# DACV5.net
KiCad netlist of a schematic drawn in EAGLE
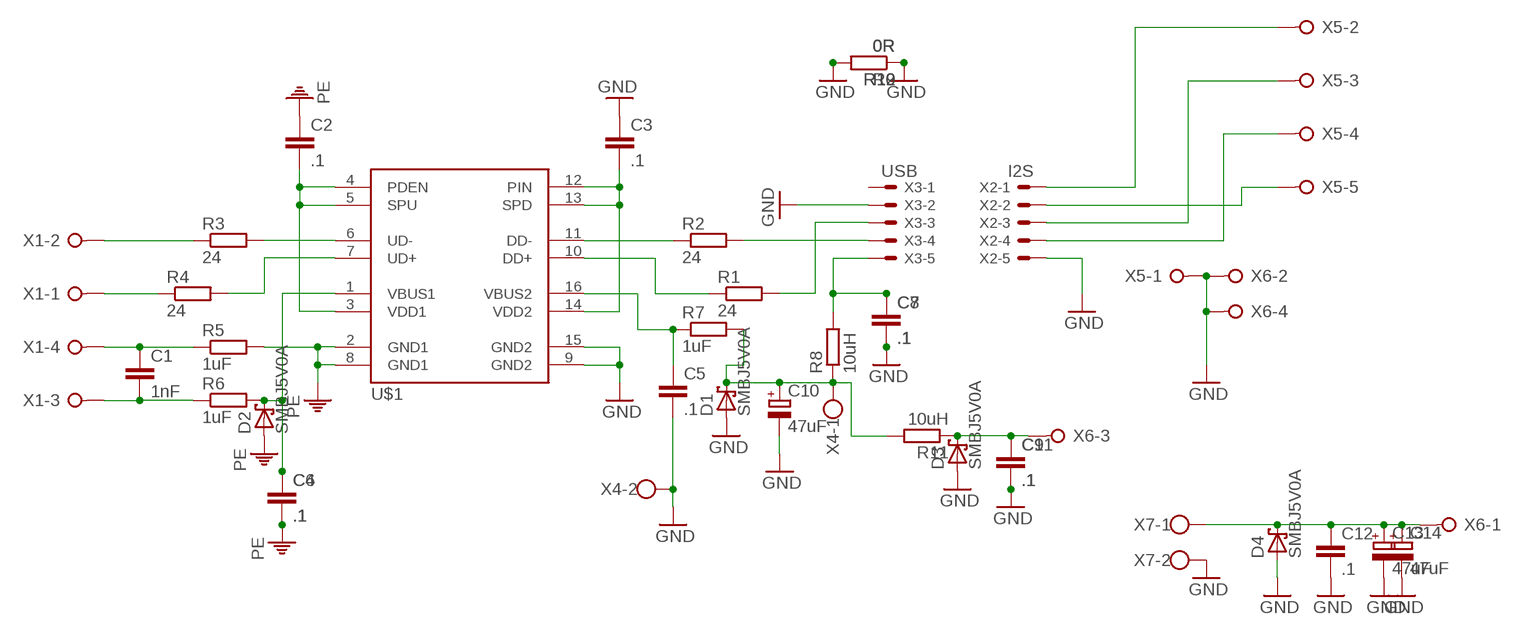
[diagram p0: schematic, sheet 1]

(export (version "E")
  (design (tool "Eeschema 10.0.6"))
  (components
    (comp (ref "C1")
      (value "1nF")
      (footprint "eagle-import:C1210")
      (libsource (lib "eagle-import") (part "C-EUC1210"))
    )
    (comp (ref "C2")
      (value ".1")
      (footprint "eagle-import:C1210")
      (libsource (lib "eagle-import") (part "C-EUC1210"))
    )
    (comp (ref "C3")
      (value ".1")
      (footprint "eagle-import:C1210")
      (libsource (lib "eagle-import") (part "C-EUC1210"))
    )
    (comp (ref "C4")
      (value ".1")
      (footprint "eagle-import:C1210")
      (libsource (lib "eagle-import") (part "C-EUC1210"))
    )
    (comp (ref "C5")
      (value ".1")
      (footprint "eagle-import:C1210")
      (libsource (lib "eagle-import") (part "C-EUC1210"))
    )
    (comp (ref "C6")
      (value ".1")
      (footprint "eagle-import:C1210")
      (libsource (lib "eagle-import") (part "C-EUC1210"))
    )
    (comp (ref "C7")
      (value ".1")
      (footprint "eagle-import:C1210")
      (libsource (lib "eagle-import") (part "C-EUC1210"))
    )
    (comp (ref "C8")
      (value ".1")
      (footprint "eagle-import:C1210")
      (libsource (lib "eagle-import") (part "C-EUC1210"))
    )
    (comp (ref "C9")
      (value ".1")
      (footprint "eagle-import:C1210")
      (libsource (lib "eagle-import") (part "C-EUC1210"))
    )
    (comp (ref "C10")
      (value "47uF")
      (footprint "eagle-import:E5-13")
      (libsource (lib "eagle-import") (part "CPOL-EUE5-13"))
    )
    (comp (ref "C11")
      (value ".1")
      (footprint "eagle-import:C1210")
      (libsource (lib "eagle-import") (part "C-EUC1210"))
    )
    (comp (ref "C12")
      (value ".1")
      (footprint "eagle-import:C1210")
      (libsource (lib "eagle-import") (part "C-EUC1210"))
    )
    (comp (ref "C13")
      (value "47uF")
      (footprint "eagle-import:E5-13")
      (libsource (lib "eagle-import") (part "CPOL-EUE5-13"))
    )
    (comp (ref "C14")
      (value "47uF")
      (footprint "eagle-import:E5-13")
      (libsource (lib "eagle-import") (part "CPOL-EUE5-13"))
    )
    (comp (ref "D1")
      (value "SMBJ5V0A")
      (footprint "eagle-import:SMB")
      (libsource (lib "eagle-import") (part "MBRS130LT3"))
    )
    (comp (ref "D2")
      (value "SMBJ5V0A")
      (footprint "eagle-import:SMB")
      (libsource (lib "eagle-import") (part "MBRS130LT3"))
    )
    (comp (ref "D3")
      (value "SMBJ5V0A")
      (footprint "eagle-import:SMB")
      (libsource (lib "eagle-import") (part "MBRS130LT3"))
    )
    (comp (ref "D4")
      (value "SMBJ5V0A")
      (footprint "eagle-import:SMB")
      (libsource (lib "eagle-import") (part "MBRS130LT3"))
    )
    (comp (ref "R1")
      (value "24")
      (footprint "eagle-import:R1210")
      (libsource (lib "eagle-import") (part "R-EU_R1210"))
    )
    (comp (ref "R2")
      (value "24")
      (footprint "eagle-import:R1210")
      (libsource (lib "eagle-import") (part "R-EU_R1210"))
    )
    (comp (ref "R3")
      (value "24")
      (footprint "eagle-import:R1210")
      (libsource (lib "eagle-import") (part "R-EU_R1210"))
    )
    (comp (ref "R4")
      (value "24")
      (footprint "eagle-import:R1210")
      (libsource (lib "eagle-import") (part "R-EU_R1210"))
    )
    (comp (ref "R5")
      (value "1uF")
      (footprint "eagle-import:R1210")
      (libsource (lib "eagle-import") (part "R-EU_R1210"))
    )
    (comp (ref "R6")
      (value "1uF")
      (footprint "eagle-import:R1210")
      (libsource (lib "eagle-import") (part "R-EU_R1210"))
    )
    (comp (ref "R7")
      (value "1uF")
      (footprint "eagle-import:R1210")
      (libsource (lib "eagle-import") (part "R-EU_R1210"))
    )
    (comp (ref "R8")
      (value "10uH")
      (footprint "eagle-import:0309_12")
      (libsource (lib "eagle-import") (part "R-EU_0309/12"))
    )
    (comp (ref "R9")
      (value "0R")
      (footprint "eagle-import:0309_12")
      (libsource (lib "eagle-import") (part "R-EU_0309/12"))
    )
    (comp (ref "R10")
      (value "0R")
      (footprint "eagle-import:0309_12")
      (libsource (lib "eagle-import") (part "R-EU_0309/12"))
    )
    (comp (ref "R11")
      (value "10uH")
      (footprint "eagle-import:0309_12")
      (libsource (lib "eagle-import") (part "R-EU_0309/12"))
    )
    (comp (ref "R12")
      (value "0R")
      (footprint "eagle-import:0309_12")
      (libsource (lib "eagle-import") (part "R-EU_0309/12"))
    )
    (comp (ref "U$1")
      (value "ADUM4160")
      (footprint "eagle-import:SO16W")
      (libsource (lib "eagle-import") (part "ADUM4160"))
    )
    (comp (ref "X1")
      (value "W237-04P")
      (footprint "eagle-import:W237-4P")
      (libsource (lib "eagle-import") (part "W237-04P"))
    )
    (comp (ref "X2")
      (value "I2S")
      (footprint "eagle-import:22-23-2051")
      (fields (field (name "MF") "MOLEX") (field (name "MPN") "22-23-2051"))
      (libsource (lib "eagle-import") (part "22-23-2051"))
    )
    (comp (ref "X3")
      (value "USB")
      (footprint "eagle-import:22-23-2051")
      (fields (field (name "MF") "MOLEX") (field (name "MPN") "22-23-2051"))
      (libsource (lib "eagle-import") (part "22-23-2051"))
    )
    (comp (ref "X4")
      (value "W237-102")
      (footprint "eagle-import:W237-102")
      (fields (field (name "MPN") "237-102"))
      (libsource (lib "eagle-import") (part "W237-102"))
    )
    (comp (ref "X5")
      (value "W237-05P")
      (footprint "eagle-import:W237-5P")
      (libsource (lib "eagle-import") (part "W237-05P"))
    )
    (comp (ref "X6")
      (value "W237-04P")
      (footprint "eagle-import:W237-4P")
      (libsource (lib "eagle-import") (part "W237-04P"))
    )
    (comp (ref "X7")
      (value "W237-102")
      (footprint "eagle-import:W237-102")
      (fields
        (field (name "MPN") "237-102")
        (field (name "MPN_1") "237-102")
        (field (name "OC_FARNELL") "unknown")
        (field (name "OC_NEWARK") "70K9898")
      )
      (libsource (lib "eagle-import") (part "W237-102"))
    )
  )
  (nets
    (net (code "1") (name "GND") (class "Default")
      (node (ref "C10") (pin "-") (pinfunction "-_-") (pintype "passive"))
      (node (ref "C11") (pin "2") (pinfunction "2_2") (pintype "passive"))
      (node (ref "C12") (pin "2") (pinfunction "2_2") (pintype "passive"))
      (node (ref "C13") (pin "-") (pinfunction "-_-") (pintype "passive"))
      (node (ref "C14") (pin "-") (pinfunction "-_-") (pintype "passive"))
      (node (ref "C3") (pin "1") (pinfunction "1_1") (pintype "passive"))
      (node (ref "C5") (pin "2") (pinfunction "2_2") (pintype "passive"))
      (node (ref "C7") (pin "2") (pinfunction "2_2") (pintype "passive"))
      (node (ref "C8") (pin "2") (pinfunction "2_2") (pintype "passive"))
      (node (ref "C9") (pin "2") (pinfunction "2_2") (pintype "passive"))
      (node (ref "D1") (pin "A") (pinfunction "A_A") (pintype "passive"))
      (node (ref "D3") (pin "A") (pinfunction "A_A") (pintype "passive"))
      (node (ref "D4") (pin "A") (pinfunction "A_A") (pintype "passive"))
      (node (ref "R10") (pin "1") (pinfunction "1_1") (pintype "passive"))
      (node (ref "R10") (pin "2") (pinfunction "2_2") (pintype "passive"))
      (node (ref "R12") (pin "1") (pinfunction "1_1") (pintype "passive"))
      (node (ref "R12") (pin "2") (pinfunction "2_2") (pintype "passive"))
      (node (ref "R9") (pin "1") (pinfunction "1_1") (pintype "passive"))
      (node (ref "R9") (pin "2") (pinfunction "2_2") (pintype "passive"))
      (node (ref "U$1") (pin "15") (pinfunction "GND2_15") (pintype "passive"))
      (node (ref "U$1") (pin "9") (pinfunction "GND2_9") (pintype "passive"))
      (node (ref "X2") (pin "5") (pinfunction "S_5") (pintype "passive"))
      (node (ref "X3") (pin "2") (pinfunction "S_2") (pintype "passive"))
      (node (ref "X4") (pin "2") (pinfunction "KL_2") (pintype "passive"))
      (node (ref "X5") (pin "1") (pinfunction "KL_1") (pintype "passive"))
      (node (ref "X6") (pin "2") (pinfunction "KL_2") (pintype "passive"))
      (node (ref "X6") (pin "4") (pinfunction "KL_4") (pintype "passive"))
      (node (ref "X7") (pin "2") (pinfunction "KL_2") (pintype "passive"))
    )
    (net (code "2") (name "Net-(U$1-DD+)") (class "Default")
      (node (ref "R1") (pin "1") (pinfunction "1_1") (pintype "passive"))
      (node (ref "U$1") (pin "10") (pinfunction "DD+_10") (pintype "bidirectional"))
    )
    (net (code "3") (name "Net-(U$1-DD-)") (class "Default")
      (node (ref "R2") (pin "1") (pinfunction "1_1") (pintype "passive"))
      (node (ref "U$1") (pin "11") (pinfunction "DD-_11") (pintype "bidirectional"))
    )
    (net (code "4") (name "Net-(U$1-PDEN)") (class "Default")
      (node (ref "C2") (pin "2") (pinfunction "2_2") (pintype "passive"))
      (node (ref "U$1") (pin "3") (pinfunction "VDD1_3") (pintype "power_in"))
      (node (ref "U$1") (pin "4") (pinfunction "PDEN_4") (pintype "input"))
      (node (ref "U$1") (pin "5") (pinfunction "SPU_5") (pintype "input"))
    )
    (net (code "5") (name "Net-(U$1-PIN)") (class "Default")
      (node (ref "C3") (pin "2") (pinfunction "2_2") (pintype "passive"))
      (node (ref "U$1") (pin "12") (pinfunction "PIN_12") (pintype "input"))
      (node (ref "U$1") (pin "13") (pinfunction "SPD_13") (pintype "input"))
      (node (ref "U$1") (pin "14") (pinfunction "VDD2_14") (pintype "power_in"))
    )
    (net (code "6") (name "Net-(U$1-UD+)") (class "Default")
      (node (ref "R4") (pin "2") (pinfunction "2_2") (pintype "passive"))
      (node (ref "U$1") (pin "7") (pinfunction "UD+_7") (pintype "bidirectional"))
    )
    (net (code "7") (name "Net-(U$1-UD-)") (class "Default")
      (node (ref "R3") (pin "2") (pinfunction "2_2") (pintype "passive"))
      (node (ref "U$1") (pin "6") (pinfunction "UD-_6") (pintype "bidirectional"))
    )
    (net (code "8") (name "Net-(U$1-VBUS1)") (class "Default")
      (node (ref "C4") (pin "1") (pinfunction "1_1") (pintype "passive"))
      (node (ref "C6") (pin "1") (pinfunction "1_1") (pintype "passive"))
      (node (ref "D2") (pin "C") (pinfunction "C_C") (pintype "passive"))
      (node (ref "R6") (pin "2") (pinfunction "2_2") (pintype "passive"))
      (node (ref "U$1") (pin "1") (pinfunction "VBUS1_1") (pintype "power_in"))
    )
    (net (code "9") (name "Net-(U$1-VBUS2)") (class "Default")
      (node (ref "C5") (pin "1") (pinfunction "1_1") (pintype "passive"))
      (node (ref "R7") (pin "1") (pinfunction "1_1") (pintype "passive"))
      (node (ref "U$1") (pin "16") (pinfunction "VBUS2_16") (pintype "power_in"))
    )
    (net (code "10") (name "Net-(X1A-KL)") (class "Default")
      (node (ref "R4") (pin "1") (pinfunction "1_1") (pintype "passive"))
      (node (ref "X1") (pin "1") (pinfunction "KL_1") (pintype "passive"))
    )
    (net (code "11") (name "Net-(X1B-KL)") (class "Default")
      (node (ref "R3") (pin "1") (pinfunction "1_1") (pintype "passive"))
      (node (ref "X1") (pin "2") (pinfunction "KL_2") (pintype "passive"))
    )
    (net (code "12") (name "Net-(X1C-KL)") (class "Default")
      (node (ref "C1") (pin "2") (pinfunction "2_2") (pintype "passive"))
      (node (ref "R6") (pin "1") (pinfunction "1_1") (pintype "passive"))
      (node (ref "X1") (pin "3") (pinfunction "KL_3") (pintype "passive"))
    )
    (net (code "13") (name "Net-(X1D-KL)") (class "Default")
      (node (ref "C1") (pin "1") (pinfunction "1_1") (pintype "passive"))
      (node (ref "R5") (pin "1") (pinfunction "1_1") (pintype "passive"))
      (node (ref "X1") (pin "4") (pinfunction "KL_4") (pintype "passive"))
    )
    (net (code "14") (name "Net-(X2A-S)") (class "Default")
      (node (ref "X2") (pin "1") (pinfunction "S_1") (pintype "passive"))
      (node (ref "X5") (pin "2") (pinfunction "KL_2") (pintype "passive"))
    )
    (net (code "15") (name "Net-(X2B-S)") (class "Default")
      (node (ref "X2") (pin "2") (pinfunction "S_2") (pintype "passive"))
      (node (ref "X5") (pin "5") (pinfunction "KL_5") (pintype "passive"))
    )
    (net (code "16") (name "Net-(X2C-S)") (class "Default")
      (node (ref "X2") (pin "3") (pinfunction "S_3") (pintype "passive"))
      (node (ref "X5") (pin "3") (pinfunction "KL_3") (pintype "passive"))
    )
    (net (code "17") (name "Net-(X2D-S)") (class "Default")
      (node (ref "X2") (pin "4") (pinfunction "S_4") (pintype "passive"))
      (node (ref "X5") (pin "4") (pinfunction "KL_4") (pintype "passive"))
    )
    (net (code "18") (name "Net-(X3C-S)") (class "Default")
      (node (ref "R1") (pin "2") (pinfunction "2_2") (pintype "passive"))
      (node (ref "X3") (pin "3") (pinfunction "S_3") (pintype "passive"))
    )
    (net (code "19") (name "Net-(X3D-S)") (class "Default")
      (node (ref "R2") (pin "2") (pinfunction "2_2") (pintype "passive"))
      (node (ref "X3") (pin "4") (pinfunction "S_4") (pintype "passive"))
    )
    (net (code "20") (name "Net-(X3E-S)") (class "Default")
      (node (ref "C7") (pin "1") (pinfunction "1_1") (pintype "passive"))
      (node (ref "C8") (pin "1") (pinfunction "1_1") (pintype "passive"))
      (node (ref "R8") (pin "2") (pinfunction "2_2") (pintype "passive"))
      (node (ref "X3") (pin "5") (pinfunction "S_5") (pintype "passive"))
    )
    (net (code "21") (name "Net-(X4A-KL)") (class "Default")
      (node (ref "C10") (pin "+") (pinfunction "+_+") (pintype "passive"))
      (node (ref "D1") (pin "C") (pinfunction "C_C") (pintype "passive"))
      (node (ref "R11") (pin "2") (pinfunction "2_2") (pintype "passive"))
      (node (ref "R7") (pin "2") (pinfunction "2_2") (pintype "passive"))
      (node (ref "R8") (pin "1") (pinfunction "1_1") (pintype "passive"))
      (node (ref "X4") (pin "1") (pinfunction "KL_1") (pintype "passive"))
    )
    (net (code "22") (name "Net-(X6A-KL)") (class "Default")
      (node (ref "C12") (pin "1") (pinfunction "1_1") (pintype "passive"))
      (node (ref "C13") (pin "+") (pinfunction "+_+") (pintype "passive"))
      (node (ref "C14") (pin "+") (pinfunction "+_+") (pintype "passive"))
      (node (ref "D4") (pin "C") (pinfunction "C_C") (pintype "passive"))
      (node (ref "X6") (pin "1") (pinfunction "KL_1") (pintype "passive"))
      (node (ref "X7") (pin "1") (pinfunction "KL_1") (pintype "passive"))
    )
    (net (code "23") (name "Net-(X6C-KL)") (class "Default")
      (node (ref "C11") (pin "1") (pinfunction "1_1") (pintype "passive"))
      (node (ref "C9") (pin "1") (pinfunction "1_1") (pintype "passive"))
      (node (ref "D3") (pin "C") (pinfunction "C_C") (pintype "passive"))
      (node (ref "R11") (pin "1") (pinfunction "1_1") (pintype "passive"))
      (node (ref "X6") (pin "3") (pinfunction "KL_3") (pintype "passive"))
    )
    (net (code "24") (name "PE") (class "Default")
      (node (ref "C2") (pin "1") (pinfunction "1_1") (pintype "passive"))
      (node (ref "C4") (pin "2") (pinfunction "2_2") (pintype "passive"))
      (node (ref "C6") (pin "2") (pinfunction "2_2") (pintype "passive"))
      (node (ref "D2") (pin "A") (pinfunction "A_A") (pintype "passive"))
      (node (ref "R5") (pin "2") (pinfunction "2_2") (pintype "passive"))
      (node (ref "U$1") (pin "2") (pinfunction "GND1_2") (pintype "passive"))
      (node (ref "U$1") (pin "8") (pinfunction "GND1_8") (pintype "passive"))
    )
    (net (code "25") (name "unconnected-(X3A-S-Pad1)") (class "Default")
      (node (ref "X3") (pin "1") (pinfunction "S_1") (pintype "passive"))
    )
  )
)
